# design.net
KiCad netlist of a schematic drawn in Altium Designer
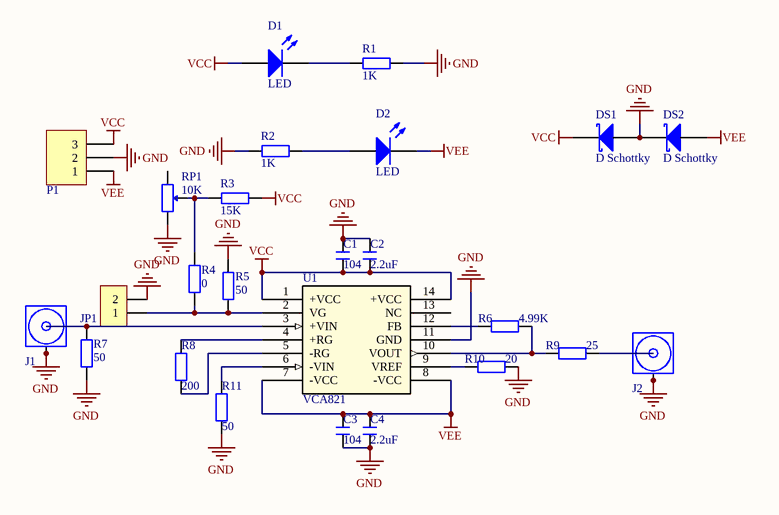
[diagram p0: 压控放大器.SchDoc]

(export (version "E")
  (design (tool "Eeschema 10.0.6"))
  (components
    (comp (ref "C1")
      (value "104")
      (footprint "C 0603")
      (description "无极性贴片电容")
      (fields (field (name "版权归属") "源创客"))
      (libsource (lib "电阻-电容-电感") (part "C"))
    )
    (comp (ref "C2")
      (value "2.2uF")
      (footprint "C 0603")
      (description "无极性贴片电容")
      (fields (field (name "版权归属") "源创客"))
      (libsource (lib "电阻-电容-电感") (part "C"))
    )
    (comp (ref "C3")
      (value "104")
      (footprint "C 0603")
      (description "无极性贴片电容")
      (fields (field (name "版权归属") "源创客"))
      (libsource (lib "电阻-电容-电感") (part "C"))
    )
    (comp (ref "C4")
      (value "2.2uF")
      (footprint "C 0603")
      (description "无极性贴片电容")
      (fields (field (name "版权归属") "源创客"))
      (libsource (lib "电阻-电容-电感") (part "C"))
    )
    (comp (ref "D1")
      (value "LED")
      (footprint "LED_0805")
      (description "发光二极管")
      (fields (field (name "PUBLISHER") "Altium Limited"))
      (libsource (lib "LIB") (part "LED"))
    )
    (comp (ref "D2")
      (value "LED")
      (footprint "LED_0805")
      (description "发光二极管")
      (fields (field (name "PUBLISHER") "Altium Limited"))
      (libsource (lib "LIB") (part "LED"))
    )
    (comp (ref "DS1")
      (value "D Schottky")
      (footprint "DIODE-SMA")
      (description "Schottky Diode")
      (fields (field (name "PUBLISHER") "Altium Limited"))
      (libsource (lib "LIB") (part "D Schottky"))
    )
    (comp (ref "DS2")
      (value "D Schottky")
      (footprint "DIODE-SMA")
      (description "Schottky Diode")
      (fields (field (name "PUBLISHER") "Altium Limited"))
      (libsource (lib "LIB") (part "D Schottky"))
    )
    (comp (ref "J1") (value "COAX") (footprint "MCX5.08-5-H") (libsource (lib "LIB") (part "COAX")))
    (comp (ref "J2") (value "COAX") (footprint "MCX5.08-5-H") (libsource (lib "LIB") (part "COAX")))
    (comp (ref "JP1")
      (value "HDR-1X2")
      (footprint "HDR-1X2")
      (description "2P接插件")
      (fields (field (name "版权归属") "源创客"))
      (libsource (lib "接插件") (part "Header 2"))
    )
    (comp (ref "P1")
      (value "Header 3")
      (footprint "HDR3X1_B2")
      (description "接插件")
      (fields (field (name "PUBLISHER") "Altium Limited"))
      (libsource (lib "LIB") (part "Header 3"))
    )
    (comp (ref "R1")
      (value "1K")
      (footprint "R 0805")
      (description "贴片电阻")
      (fields (field (name "版权归属") "源创客"))
      (libsource (lib "电阻-电容-电感") (part "R"))
    )
    (comp (ref "R2")
      (value "1K")
      (footprint "R 0805")
      (description "贴片电阻")
      (fields (field (name "版权归属") "源创客"))
      (libsource (lib "电阻-电容-电感") (part "R"))
    )
    (comp (ref "R3")
      (value "15K")
      (footprint "R 0603")
      (description "贴片电阻")
      (fields (field (name "版权归属") "源创客"))
      (libsource (lib "电阻-电容-电感") (part "R"))
    )
    (comp (ref "R4")
      (value "0")
      (footprint "R 0603")
      (description "贴片电阻")
      (fields (field (name "版权归属") "源创客"))
      (libsource (lib "电阻-电容-电感") (part "R"))
    )
    (comp (ref "R5")
      (value "50")
      (footprint "R 0603")
      (description "贴片电阻")
      (fields (field (name "版权归属") "源创客"))
      (libsource (lib "电阻-电容-电感") (part "R"))
    )
    (comp (ref "R6")
      (value "4.99K")
      (footprint "R 0603")
      (description "贴片电阻")
      (fields (field (name "版权归属") "源创客"))
      (libsource (lib "电阻-电容-电感") (part "R"))
    )
    (comp (ref "R7")
      (value "50")
      (footprint "R 0603")
      (description "贴片电阻")
      (fields (field (name "版权归属") "源创客"))
      (libsource (lib "电阻-电容-电感") (part "R"))
    )
    (comp (ref "R8")
      (value "200")
      (footprint "R 0603")
      (description "贴片电阻")
      (fields (field (name "版权归属") "源创客"))
      (libsource (lib "电阻-电容-电感") (part "R"))
    )
    (comp (ref "R9")
      (value "25")
      (footprint "R 0603")
      (description "贴片电阻")
      (fields (field (name "版权归属") "源创客"))
      (libsource (lib "电阻-电容-电感") (part "R"))
    )
    (comp (ref "R10")
      (value "20")
      (footprint "R 0603")
      (description "贴片电阻")
      (fields (field (name "版权归属") "源创客"))
      (libsource (lib "电阻-电容-电感") (part "R"))
    )
    (comp (ref "R11")
      (value "50")
      (footprint "R 0603")
      (description "贴片电阻")
      (fields (field (name "版权归属") "源创客"))
      (libsource (lib "电阻-电容-电感") (part "R"))
    )
    (comp (ref "RP1")
      (value "10K")
      (footprint "3296W")
      (description "插件单联电位器")
      (fields (field (name "版权归属") "源创客"))
      (libsource (lib "电阻-电容-电感") (part "RP-ID"))
    )
    (comp (ref "U1")
      (value "VCA821")
      (footprint "SOIC14_N")
      (description "可变增益放大器 Ultra-Wideband, > 40-dB Gain Adjust Range, Linear in dB")
      (fields
        (field (name "MANUFACTURER") "Texas Instruments")
        (field (name "MANUFACTURER_PART_NUMBER") "vca821_d_14")
      )
      (libsource (lib "LIB") (part "VCA821"))
    )
  )
  (nets
    (net (code "1") (name "GND") (class "Default")
      (node (ref "C1") (pin "2") (pinfunction "2_2") (pintype "passive"))
      (node (ref "C2") (pin "2") (pinfunction "2_2") (pintype "passive"))
      (node (ref "C3") (pin "2") (pinfunction "2_2") (pintype "passive"))
      (node (ref "C4") (pin "1") (pinfunction "1_1") (pintype "passive"))
      (node (ref "DS1") (pin "1") (pinfunction "1_1") (pintype "passive"))
      (node (ref "DS2") (pin "2") (pinfunction "2_2") (pintype "passive"))
      (node (ref "J1") (pin "2") (pinfunction "GND_2") (pintype "passive"))
      (node (ref "J1") (pin "3") (pinfunction "GND_3") (pintype "passive"))
      (node (ref "J1") (pin "4") (pinfunction "GND_4") (pintype "passive"))
      (node (ref "J1") (pin "5") (pinfunction "GND_5") (pintype "passive"))
      (node (ref "J2") (pin "2") (pinfunction "GND_2") (pintype "passive"))
      (node (ref "J2") (pin "3") (pinfunction "GND_3") (pintype "passive"))
      (node (ref "J2") (pin "4") (pinfunction "GND_4") (pintype "passive"))
      (node (ref "J2") (pin "5") (pinfunction "GND_5") (pintype "passive"))
      (node (ref "JP1") (pin "2") (pinfunction "2_2") (pintype "passive"))
      (node (ref "P1") (pin "2") (pinfunction "2_2") (pintype "passive"))
      (node (ref "R1") (pin "2") (pinfunction "2_2") (pintype "passive"))
      (node (ref "R10") (pin "2") (pinfunction "2_2") (pintype "passive"))
      (node (ref "R11") (pin "1") (pinfunction "1_1") (pintype "passive"))
      (node (ref "R2") (pin "1") (pinfunction "1_1") (pintype "passive"))
      (node (ref "R5") (pin "1") (pinfunction "1_1") (pintype "passive"))
      (node (ref "R7") (pin "1") (pinfunction "1_1") (pintype "passive"))
      (node (ref "RP1") (pin "3") (pinfunction "3_3") (pintype "passive"))
      (node (ref "U1") (pin "11") (pinfunction "GND_11") (pintype "power_in"))
    )
    (net (code "2") (name "Net-(D1-K)") (class "Default")
      (node (ref "D1") (pin "2") (pinfunction "K_2") (pintype "passive"))
      (node (ref "R1") (pin "1") (pinfunction "1_1") (pintype "passive"))
    )
    (net (code "3") (name "Net-(D2-A)") (class "Default")
      (node (ref "D2") (pin "1") (pinfunction "A_1") (pintype "passive"))
      (node (ref "R2") (pin "2") (pinfunction "2_2") (pintype "passive"))
    )
    (net (code "4") (name "Net-(J1-Signal)") (class "Default")
      (node (ref "J1") (pin "1") (pinfunction "Signal_1") (pintype "passive"))
      (node (ref "R7") (pin "2") (pinfunction "2_2") (pintype "passive"))
      (node (ref "U1") (pin "3") (pinfunction "+VIN_3") (pintype "input"))
    )
    (net (code "5") (name "Net-(J2-Signal)") (class "Default")
      (node (ref "J2") (pin "1") (pinfunction "Signal_1") (pintype "passive"))
      (node (ref "R9") (pin "2") (pinfunction "2_2") (pintype "passive"))
    )
    (net (code "6") (name "Net-(R3-Pad1)") (class "Default")
      (node (ref "R3") (pin "1") (pinfunction "1_1") (pintype "passive"))
      (node (ref "R4") (pin "2") (pinfunction "2_2") (pintype "passive"))
      (node (ref "RP1") (pin "2") (pinfunction "2_2") (pintype "passive"))
    )
    (net (code "7") (name "Net-(U1-+RG)") (class "Default")
      (node (ref "R8") (pin "2") (pinfunction "2_2") (pintype "passive"))
      (node (ref "U1") (pin "4") (pinfunction "+RG_4") (pintype "passive"))
    )
    (net (code "8") (name "Net-(U1--RG)") (class "Default")
      (node (ref "R8") (pin "1") (pinfunction "1_1") (pintype "passive"))
      (node (ref "U1") (pin "5") (pinfunction "-RG_5") (pintype "passive"))
    )
    (net (code "9") (name "Net-(U1--VIN)") (class "Default")
      (node (ref "R11") (pin "2") (pinfunction "2_2") (pintype "passive"))
      (node (ref "U1") (pin "6") (pinfunction "-VIN_6") (pintype "input"))
    )
    (net (code "10") (name "Net-(U1-FB)") (class "Default")
      (node (ref "R6") (pin "1") (pinfunction "1_1") (pintype "passive"))
      (node (ref "U1") (pin "12") (pinfunction "FB_12") (pintype "passive"))
    )
    (net (code "11") (name "Net-(U1-VG)") (class "Default")
      (node (ref "JP1") (pin "1") (pinfunction "1_1") (pintype "passive"))
      (node (ref "R4") (pin "1") (pinfunction "1_1") (pintype "passive"))
      (node (ref "R5") (pin "2") (pinfunction "2_2") (pintype "passive"))
      (node (ref "U1") (pin "2") (pinfunction "VG_2") (pintype "passive"))
    )
    (net (code "12") (name "Net-(U1-VOUT)") (class "Default")
      (node (ref "R6") (pin "2") (pinfunction "2_2") (pintype "passive"))
      (node (ref "R9") (pin "1") (pinfunction "1_1") (pintype "passive"))
      (node (ref "U1") (pin "10") (pinfunction "VOUT_10") (pintype "output"))
    )
    (net (code "13") (name "Net-(U1-VREF)") (class "Default")
      (node (ref "R10") (pin "1") (pinfunction "1_1") (pintype "passive"))
      (node (ref "U1") (pin "9") (pinfunction "VREF_9") (pintype "passive"))
    )
    (net (code "14") (name "VCC") (class "Default")
      (node (ref "C1") (pin "1") (pinfunction "1_1") (pintype "passive"))
      (node (ref "C2") (pin "1") (pinfunction "1_1") (pintype "passive"))
      (node (ref "D1") (pin "1") (pinfunction "A_1") (pintype "passive"))
      (node (ref "DS1") (pin "2") (pinfunction "2_2") (pintype "passive"))
      (node (ref "P1") (pin "3") (pinfunction "3_3") (pintype "passive"))
      (node (ref "R3") (pin "2") (pinfunction "2_2") (pintype "passive"))
      (node (ref "U1") (pin "1") (pinfunction "+VCC_1") (pintype "power_in"))
      (node (ref "U1") (pin "14") (pinfunction "+VCC_14") (pintype "power_in"))
    )
    (net (code "15") (name "VEE") (class "Default")
      (node (ref "C3") (pin "1") (pinfunction "1_1") (pintype "passive"))
      (node (ref "C4") (pin "2") (pinfunction "2_2") (pintype "passive"))
      (node (ref "D2") (pin "2") (pinfunction "K_2") (pintype "passive"))
      (node (ref "DS2") (pin "1") (pinfunction "1_1") (pintype "passive"))
      (node (ref "P1") (pin "1") (pinfunction "1_1") (pintype "passive"))
      (node (ref "U1") (pin "7") (pinfunction "-VCC_7") (pintype "power_in"))
      (node (ref "U1") (pin "8") (pinfunction "-VCC_8") (pintype "power_in"))
    )
    (net (code "16") (name "unconnected-(RP1-Pad1)") (class "Default")
      (node (ref "RP1") (pin "1") (pinfunction "1_1") (pintype "passive"))
    )
    (net (code "17") (name "unconnected-(U1-NC-Pad13)") (class "Default")
      (node (ref "U1") (pin "13") (pinfunction "NC_13") (pintype "passive"))
    )
  )
)
